# TSAL.net
KiCad netlist of a schematic drawn in Altium Designer
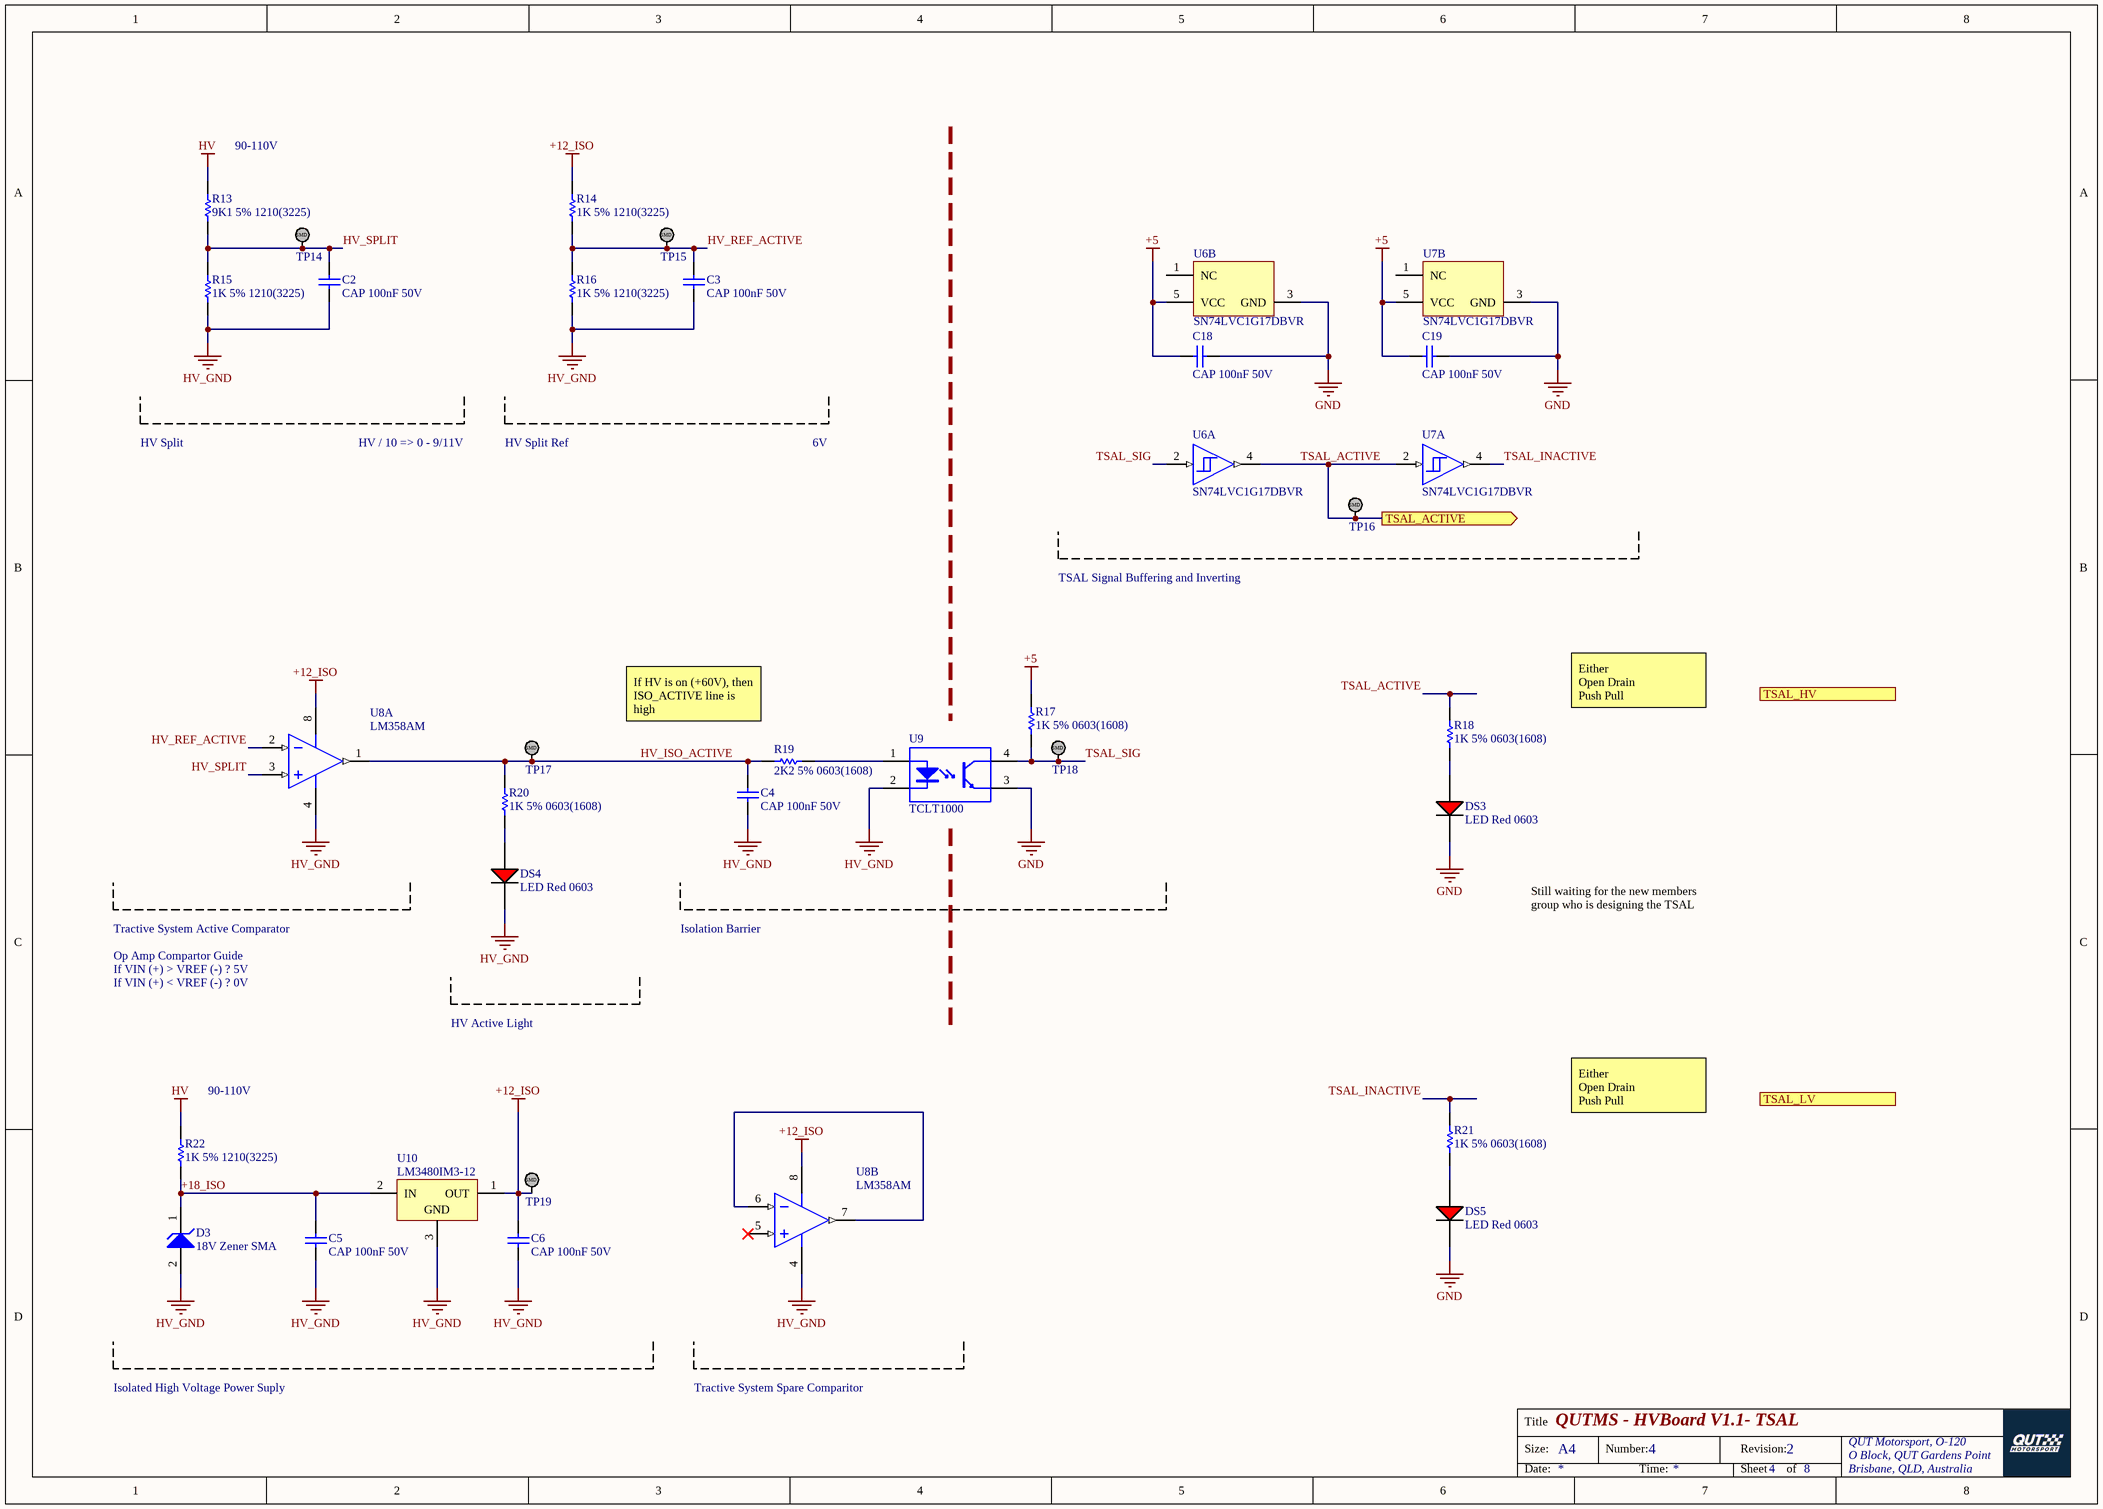
[diagram p0: TSAL.SchDoc]

(export (version "E")
  (design (tool "Eeschema 10.0.6"))
  (components
    (comp (ref "C2")
      (value "CAP 100nF 50V")
      (footprint "CAPC0603(1608)100_N")
      (description "CAP 100nF 50V ±5% 0603 (1608 Metric) Thickness 1mm SMD")
      (fields (field (name "TOLERANCE") "Â±5%"))
      (libsource (lib "Altium Content Vault") (part "CAP"))
    )
    (comp (ref "C3")
      (value "CAP 100nF 50V")
      (footprint "CAPC0603(1608)100_N")
      (description "CAP 100nF 50V ±5% 0603 (1608 Metric) Thickness 1mm SMD")
      (fields (field (name "TOLERANCE") "Â±5%"))
      (libsource (lib "Altium Content Vault") (part "CAP"))
    )
    (comp (ref "C4")
      (value "CAP 100nF 50V")
      (footprint "CAPC0603(1608)100_N")
      (description "CAP 100nF 50V ±5% 0603 (1608 Metric) Thickness 1mm SMD")
      (fields (field (name "TOLERANCE") "Â±5%"))
      (libsource (lib "Altium Content Vault") (part "CAP"))
    )
    (comp (ref "C5")
      (value "CAP 100nF 50V")
      (footprint "CAPC0603(1608)100_N")
      (description "CAP 100nF 50V ±5% 0603 (1608 Metric) Thickness 1mm SMD")
      (fields (field (name "TOLERANCE") "Â±5%"))
      (libsource (lib "Altium Content Vault") (part "CAP"))
    )
    (comp (ref "C6")
      (value "CAP 100nF 50V")
      (footprint "CAPC0603(1608)100_N")
      (description "CAP 100nF 50V ±5% 0603 (1608 Metric) Thickness 1mm SMD")
      (fields (field (name "TOLERANCE") "Â±5%"))
      (libsource (lib "Altium Content Vault") (part "CAP"))
    )
    (comp (ref "C18")
      (value "CAP 100nF 50V")
      (footprint "CAPC0603(1608)100_N")
      (description "CAP 100nF 50V ±5% 0603 (1608 Metric) Thickness 1mm SMD")
      (fields (field (name "TOLERANCE") "Â±5%"))
      (libsource (lib "Altium Content Vault") (part "CAP"))
    )
    (comp (ref "C19")
      (value "CAP 100nF 50V")
      (footprint "CAPC0603(1608)100_N")
      (description "CAP 100nF 50V ±5% 0603 (1608 Metric) Thickness 1mm SMD")
      (fields (field (name "TOLERANCE") "Â±5%"))
      (libsource (lib "Altium Content Vault") (part "CAP"))
    )
    (comp (ref "D3")
      (value "18V Zener SMA")
      (footprint "ONSC-SMA-2-403D-02_F_V")
      (description "1.5 W Zener Voltage Regulator, 2-Pin SMA, Pb-Free, Tape and Reel")
      (fields (field (name "MANUFACTURER") "On Semiconductor") (field (name "PARTNUMBER") "1SMA5931BT3G"))
      (libsource (lib "Altium Content Vault") (part "ONSC-K1A2-2"))
    )
    (comp (ref "DS3")
      (value "LED Red 0603")
      (footprint "LED RED 0603")
      (libsource (lib "QUTMS_LEDLibrary") (part "LED RED 0603"))
    )
    (comp (ref "DS4")
      (value "LED Red 0603")
      (footprint "LED RED 0603")
      (libsource (lib "QUTMS_LEDLibrary") (part "LED RED 0603"))
    )
    (comp (ref "DS5")
      (value "LED Red 0603")
      (footprint "LED RED 0603")
      (libsource (lib "QUTMS_LEDLibrary") (part "LED RED 0603"))
    )
    (comp (ref "R13")
      (value "9K1 5% 1210(3225)")
      (footprint "RESC1210(3225)_N")
      (description "9K1 0.5W 5% 1210 (3225 Metric)  SMD")
      (fields (field (name "POWER") "0.5 W") (field (name "TOLERANCE") "5 %"))
      (libsource (lib "Altium Content Vault") (part "RES"))
    )
    (comp (ref "R14")
      (value "1K 5% 1210(3225)")
      (footprint "RESC1210(3225)_N")
      (description "1K 0.5W 5% 1210 (3225 Metric)  SMD")
      (fields (field (name "POWER") "0.5 W") (field (name "TOLERANCE") "5 %"))
      (libsource (lib "Altium Content Vault") (part "RES"))
    )
    (comp (ref "R15")
      (value "1K 5% 1210(3225)")
      (footprint "RESC1210(3225)_N")
      (description "1K 0.5W 5% 1210 (3225 Metric)  SMD")
      (fields (field (name "POWER") "0.5 W") (field (name "TOLERANCE") "5 %"))
      (libsource (lib "Altium Content Vault") (part "RES"))
    )
    (comp (ref "R16")
      (value "1K 5% 1210(3225)")
      (footprint "RESC1210(3225)_N")
      (description "1K 0.5W 5% 1210 (3225 Metric)  SMD")
      (fields (field (name "POWER") "0.5 W") (field (name "TOLERANCE") "5 %"))
      (libsource (lib "Altium Content Vault") (part "RES"))
    )
    (comp (ref "R17")
      (value "1K 5% 0603(1608)")
      (footprint "RESC0603(1608)_L")
      (description "1K 0.1W 5% 0603 (1608 Metric)  SMD")
      (fields (field (name "TOLERANCE") "5 %") (field (name "POWER") "0.1 W"))
      (libsource (lib "Altium Content Vault") (part "RES"))
    )
    (comp (ref "R18")
      (value "1K 5% 0603(1608)")
      (footprint "RESC0603(1608)_N")
      (description "1K 0.1W 5% 0603 (1608 Metric)  SMD")
      (fields (field (name "TOLERANCE") "5 %") (field (name "POWER") "0.1 W"))
      (libsource (lib "Altium Content Vault") (part "RES"))
    )
    (comp (ref "R19")
      (value "2K2 5% 0603(1608)")
      (footprint "RESC0603(1608)_N")
      (description "2K2 0.1W 5% 0603 (1608 Metric)  SMD")
      (fields (field (name "POWER") "0.1 W") (field (name "TOLERANCE") "5 %"))
      (libsource (lib "Altium Content Vault") (part "RES"))
    )
    (comp (ref "R20")
      (value "1K 5% 0603(1608)")
      (footprint "RESC0603(1608)_N")
      (description "1K 0.1W 5% 0603 (1608 Metric)  SMD")
      (fields (field (name "TOLERANCE") "5 %") (field (name "POWER") "0.1 W"))
      (libsource (lib "Altium Content Vault") (part "RES"))
    )
    (comp (ref "R21")
      (value "1K 5% 0603(1608)")
      (footprint "RESC0603(1608)_N")
      (description "1K 0.1W 5% 0603 (1608 Metric)  SMD")
      (fields (field (name "TOLERANCE") "5 %") (field (name "POWER") "0.1 W"))
      (libsource (lib "Altium Content Vault") (part "RES"))
    )
    (comp (ref "R22")
      (value "1K 5% 1210(3225)")
      (footprint "RESC1210(3225)_N")
      (description "1K 0.5W 5% 1210 (3225 Metric)  SMD")
      (fields (field (name "POWER") "0.5 W") (field (name "TOLERANCE") "5 %"))
      (libsource (lib "Altium Content Vault") (part "RES"))
    )
    (comp (ref "TP14")
      (value "TestPoint_SMD")
      (footprint "TestPointSMD")
      (libsource (lib "StandardTest") (part "TestPoint_SMD"))
    )
    (comp (ref "TP15")
      (value "TestPoint_SMD")
      (footprint "TestPointSMD")
      (libsource (lib "StandardTest") (part "TestPoint_SMD"))
    )
    (comp (ref "TP16")
      (value "TestPoint_SMD")
      (footprint "TestPointSMD")
      (libsource (lib "StandardTest") (part "TestPoint_SMD"))
    )
    (comp (ref "TP17")
      (value "TestPoint_SMD")
      (footprint "TestPointSMD")
      (libsource (lib "StandardTest") (part "TestPoint_SMD"))
    )
    (comp (ref "TP18")
      (value "TestPoint_SMD")
      (footprint "TestPointSMD")
      (libsource (lib "StandardTest") (part "TestPoint_SMD"))
    )
    (comp (ref "TP19")
      (value "TestPoint_SMD")
      (footprint "TestPointSMD")
      (libsource (lib "StandardTest") (part "TestPoint_SMD"))
    )
    (comp (ref "U6")
      (value "SN74LVC1G17DBVR")
      (footprint "DBV0005A_N")
      (description "Single Schmitt-Trigger Buffer, DBV0005A, LARGE T&R")
      (fields
        (field (name "MANUFACTURER") "Texas Instruments")
        (field (name "GENERIC PART NUMBER") "SN74LVC1G17")
      )
      (libsource (lib "Altium Content Vault") (part "TI-SN74XXX1XXX-XX-5-SCHMITT"))
    )
    (comp (ref "U7")
      (value "SN74LVC1G17DBVR")
      (footprint "DBV0005A_N")
      (description "Single Schmitt-Trigger Buffer, DBV0005A, LARGE T&R")
      (fields
        (field (name "MANUFACTURER") "Texas Instruments")
        (field (name "GENERIC PART NUMBER") "SN74LVC1G17")
      )
      (libsource (lib "Altium Content Vault") (part "TI-SN74XXX1XXX-XX-5-SCHMITT"))
    )
    (comp (ref "U8")
      (value "LM358AM")
      (footprint "D0008A_N")
      (description "Low Power Dual Operational Amplifier, 8-pin Narrow SOIC")
      (fields (field (name "MANUFACTURER") "Texas Instruments"))
      (libsource (lib "Altium Content Vault") (part "AMP-OPA-LM158-8"))
    )
    (comp (ref "U9")
      (value "TCLT1000")
      (footprint "VISH-SOP4L-4_V")
      (fields (field (name "MANUFACTURER") "Vishay/Semiconductor"))
      (libsource (lib "Altium Content Vault") (part "OPTO-ACEC-4"))
    )
    (comp (ref "U10")
      (value "LM3480IM3-12")
      (footprint "DBZ0003A_N")
      (description "100 mA, Quasi Low-Dropout Linear Voltage Regulator, 3-pin SOT-23, Pb-Free")
      (fields (field (name "MANUFACTURER") "Texas Instruments"))
      (libsource (lib "Altium Content Vault") (part "PM-REG-LM3480-SOT3"))
    )
  )
  (nets
    (net (code "1") (name "+5") (class "Default")
      (node (ref "C18") (pin "1") (pinfunction "1_1") (pintype "passive"))
      (node (ref "C19") (pin "1") (pinfunction "1_1") (pintype "passive"))
      (node (ref "R17") (pin "2") (pinfunction "2_2") (pintype "passive"))
      (node (ref "U6") (pin "5") (pinfunction "VCC_5") (pintype "power_in"))
      (node (ref "U7") (pin "5") (pinfunction "VCC_5") (pintype "power_in"))
    )
    (net (code "2") (name "+12_ISO") (class "Default")
      (node (ref "C6") (pin "1") (pinfunction "1_1") (pintype "passive"))
      (node (ref "R14") (pin "2") (pinfunction "2_2") (pintype "passive"))
      (node (ref "TP19") (pin "1") (pinfunction "1_1") (pintype "passive"))
      (node (ref "U10") (pin "1") (pinfunction "OUT_1") (pintype "power_in"))
      (node (ref "U8") (pin "8") (pinfunction "V+_8") (pintype "power_in"))
    )
    (net (code "3") (name "/+18_ISO") (class "Default")
      (node (ref "C5") (pin "1") (pinfunction "1_1") (pintype "passive"))
      (node (ref "D3") (pin "1") (pinfunction "K_1") (pintype "passive"))
      (node (ref "R22") (pin "1") (pinfunction "1_1") (pintype "passive"))
      (node (ref "U10") (pin "2") (pinfunction "IN_2") (pintype "power_in"))
    )
    (net (code "4") (name "/HV_ISO_ACTIVE") (class "Default")
      (node (ref "C4") (pin "1") (pinfunction "1_1") (pintype "passive"))
      (node (ref "R19") (pin "2") (pinfunction "2_2") (pintype "passive"))
      (node (ref "R20") (pin "2") (pinfunction "2_2") (pintype "passive"))
      (node (ref "TP17") (pin "1") (pinfunction "1_1") (pintype "passive"))
      (node (ref "U8") (pin "1") (pinfunction "OUTA_1") (pintype "output"))
    )
    (net (code "5") (name "/HV_REF_ACTIVE") (class "Default")
      (node (ref "C3") (pin "1") (pinfunction "1_1") (pintype "passive"))
      (node (ref "R14") (pin "1") (pinfunction "1_1") (pintype "passive"))
      (node (ref "R16") (pin "2") (pinfunction "2_2") (pintype "passive"))
      (node (ref "TP15") (pin "1") (pinfunction "1_1") (pintype "passive"))
      (node (ref "U8") (pin "2") (pinfunction "INA-_2") (pintype "input"))
    )
    (net (code "6") (name "/HV_SPLIT") (class "Default")
      (node (ref "C2") (pin "1") (pinfunction "1_1") (pintype "passive"))
      (node (ref "R13") (pin "1") (pinfunction "1_1") (pintype "passive"))
      (node (ref "R15") (pin "2") (pinfunction "2_2") (pintype "passive"))
      (node (ref "TP14") (pin "1") (pinfunction "1_1") (pintype "passive"))
      (node (ref "U8") (pin "3") (pinfunction "INA+_3") (pintype "input"))
    )
    (net (code "7") (name "/TSAL_ACTIVE") (class "Default")
      (node (ref "R18") (pin "2") (pinfunction "2_2") (pintype "passive"))
      (node (ref "TP16") (pin "1") (pinfunction "1_1") (pintype "passive"))
      (node (ref "U6") (pin "4") (pinfunction "Y_4") (pintype "output"))
      (node (ref "U7") (pin "2") (pinfunction "A_2") (pintype "input"))
    )
    (net (code "9") (name "/TSAL_INACTIVE") (class "Default")
      (node (ref "R21") (pin "2") (pinfunction "2_2") (pintype "passive"))
      (node (ref "U7") (pin "4") (pinfunction "Y_4") (pintype "output"))
    )
    (net (code "11") (name "/TSAL_SIG") (class "Default")
      (node (ref "R17") (pin "1") (pinfunction "1_1") (pintype "passive"))
      (node (ref "TP18") (pin "1") (pinfunction "1_1") (pintype "passive"))
      (node (ref "U6") (pin "2") (pinfunction "A_2") (pintype "input"))
      (node (ref "U9") (pin "4") (pinfunction "C_4") (pintype "passive"))
    )
    (net (code "12") (name "GND") (class "Default")
      (node (ref "C18") (pin "2") (pinfunction "2_2") (pintype "passive"))
      (node (ref "C19") (pin "2") (pinfunction "2_2") (pintype "passive"))
      (node (ref "DS3") (pin "2") (pinfunction "C_2") (pintype "passive"))
      (node (ref "DS5") (pin "2") (pinfunction "C_2") (pintype "passive"))
      (node (ref "U6") (pin "3") (pinfunction "GND_3") (pintype "power_in"))
      (node (ref "U7") (pin "3") (pinfunction "GND_3") (pintype "power_in"))
      (node (ref "U9") (pin "3") (pinfunction "E_3") (pintype "passive"))
    )
    (net (code "13") (name "HV") (class "Default")
      (node (ref "R13") (pin "2") (pinfunction "2_2") (pintype "passive"))
      (node (ref "R22") (pin "2") (pinfunction "2_2") (pintype "passive"))
    )
    (net (code "14") (name "HV_GND") (class "Default")
      (node (ref "C2") (pin "2") (pinfunction "2_2") (pintype "passive"))
      (node (ref "C3") (pin "2") (pinfunction "2_2") (pintype "passive"))
      (node (ref "C4") (pin "2") (pinfunction "2_2") (pintype "passive"))
      (node (ref "C5") (pin "2") (pinfunction "2_2") (pintype "passive"))
      (node (ref "C6") (pin "2") (pinfunction "2_2") (pintype "passive"))
      (node (ref "D3") (pin "2") (pinfunction "A_2") (pintype "passive"))
      (node (ref "DS4") (pin "2") (pinfunction "C_2") (pintype "passive"))
      (node (ref "R15") (pin "1") (pinfunction "1_1") (pintype "passive"))
      (node (ref "R16") (pin "1") (pinfunction "1_1") (pintype "passive"))
      (node (ref "U10") (pin "3") (pinfunction "GND_3") (pintype "power_in"))
      (node (ref "U8") (pin "4") (pinfunction "GND_4") (pintype "power_in"))
      (node (ref "U9") (pin "2") (pinfunction "C_2") (pintype "passive"))
    )
    (net (code "15") (name "Net-(DS3-A)") (class "Default")
      (node (ref "DS3") (pin "1") (pinfunction "A_1") (pintype "passive"))
      (node (ref "R18") (pin "1") (pinfunction "1_1") (pintype "passive"))
    )
    (net (code "16") (name "Net-(DS4-A)") (class "Default")
      (node (ref "DS4") (pin "1") (pinfunction "A_1") (pintype "passive"))
      (node (ref "R20") (pin "1") (pinfunction "1_1") (pintype "passive"))
    )
    (net (code "17") (name "Net-(DS5-A)") (class "Default")
      (node (ref "DS5") (pin "1") (pinfunction "A_1") (pintype "passive"))
      (node (ref "R21") (pin "1") (pinfunction "1_1") (pintype "passive"))
    )
    (net (code "18") (name "Net-(U8B-INB-)") (class "Default")
      (node (ref "U8") (pin "6") (pinfunction "INB-_6") (pintype "input"))
      (node (ref "U8") (pin "7") (pinfunction "OUTB_7") (pintype "output"))
    )
    (net (code "19") (name "Net-(U9-A)") (class "Default")
      (node (ref "R19") (pin "1") (pinfunction "1_1") (pintype "passive"))
      (node (ref "U9") (pin "1") (pinfunction "A_1") (pintype "passive"))
    )
    (net (code "20") (name "unconnected-(U6B-NC-Pad1)") (class "Default")
      (node (ref "U6") (pin "1") (pinfunction "NC_1") (pintype "passive"))
    )
    (net (code "21") (name "unconnected-(U7B-NC-Pad1)") (class "Default")
      (node (ref "U7") (pin "1") (pinfunction "NC_1") (pintype "passive"))
    )
    (net (code "22") (name "unconnected-(U8B-INB+-Pad5)") (class "Default")
      (node (ref "U8") (pin "5") (pinfunction "INB+_5") (pintype "input+no_connect"))
    )
  )
)
